# ESQUEMATICO.net
KiCad netlist of a schematic drawn in Altium Designer
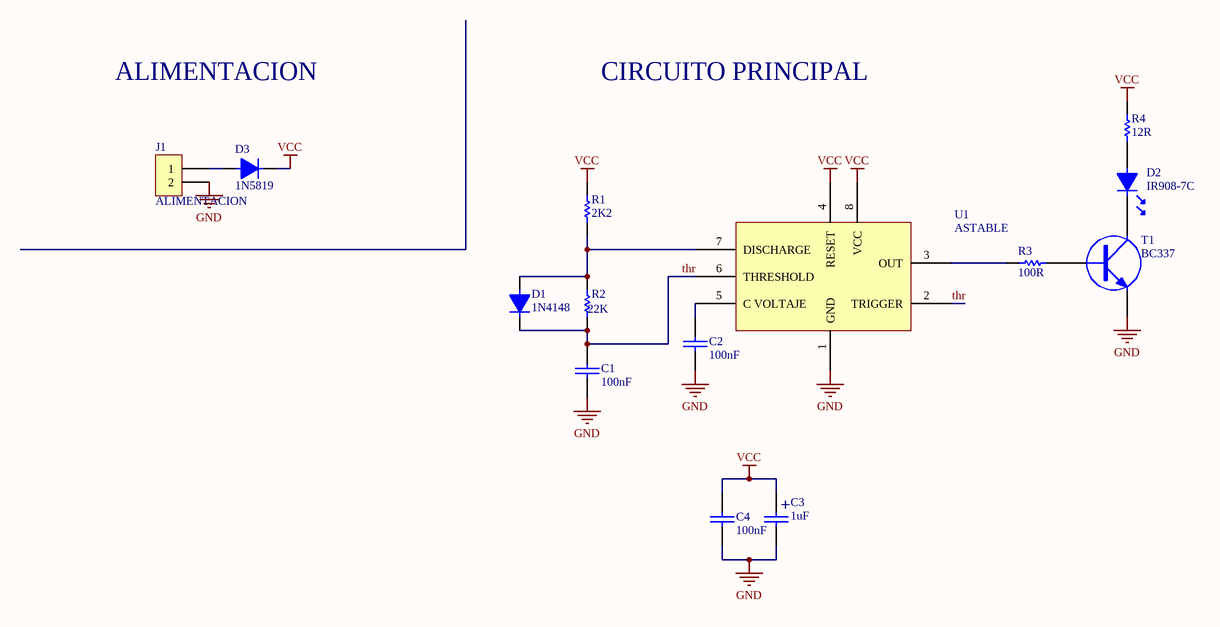
[diagram p0: ESQUEMATICO.SchDoc]

(export (version "E")
  (design (tool "Eeschema 10.0.6"))
  (components
    (comp (ref "C1") (value "100nF") (footprint "CAP100") (libsource (lib "Libreria4") (part "CAP")))
    (comp (ref "C2") (value "100nF") (footprint "CAP200") (libsource (lib "Libreria4") (part "CAP")))
    (comp (ref "C3") (value "1uF") (footprint "CAP100RP") (libsource (lib "Libreria4") (part "CAPPOL")))
    (comp (ref "C4") (value "100nF") (footprint "CAP200") (libsource (lib "Libreria4") (part "CAP")))
    (comp (ref "D1") (value "1N4148") (footprint "DO41") (libsource (lib "Libreria4") (part "DIODO")))
    (comp (ref "D2")
      (value "IR908-7C")
      (footprint "fotodiodo")
      (description "Led infrarrojo")
      (libsource (lib "Libreria4") (part "IR908-7C"))
    )
    (comp (ref "D3") (value "1N5819") (footprint "DO41") (libsource (lib "Libreria4") (part "DIODO")))
    (comp (ref "J1")
      (value "ALIMENTACION")
      (footprint "BORNERA2")
      (libsource (lib "Libreria4") (part "BORNERA 2"))
    )
    (comp (ref "R1") (value "2K2") (footprint "RES400") (libsource (lib "Libreria4") (part "RES")))
    (comp (ref "R2") (value "22K") (footprint "RES400") (libsource (lib "Libreria4") (part "RES")))
    (comp (ref "R3") (value "100R") (footprint "RES400") (libsource (lib "Libreria4") (part "RES")))
    (comp (ref "R4") (value "12R") (footprint "RES400") (libsource (lib "Libreria4") (part "RES")))
    (comp (ref "T1") (value "BC337") (footprint "TO92") (libsource (lib "Libreria4") (part "TRANSISTOR NPN")))
    (comp (ref "U1")
      (value "ASTABLE")
      (footprint "DIP8")
      (description "Timer")
      (libsource (lib "Libreria4") (part "LM555"))
    )
  )
  (nets
    (net (code "1") (name "/thr") (class "Default")
      (node (ref "C1") (pin "1") (pinfunction "1_1") (pintype "passive"))
      (node (ref "D1") (pin "2") (pinfunction "2_2") (pintype "passive"))
      (node (ref "R2") (pin "1") (pinfunction "1_1") (pintype "passive"))
      (node (ref "U1") (pin "2") (pinfunction "TRIGGER_2") (pintype "passive"))
      (node (ref "U1") (pin "6") (pinfunction "THRESHOLD_6") (pintype "passive"))
    )
    (net (code "2") (name "GND") (class "Default")
      (node (ref "C1") (pin "2") (pinfunction "2_2") (pintype "passive"))
      (node (ref "C2") (pin "2") (pinfunction "2_2") (pintype "passive"))
      (node (ref "C3") (pin "2") (pinfunction "2_2") (pintype "passive"))
      (node (ref "C4") (pin "2") (pinfunction "2_2") (pintype "passive"))
      (node (ref "J1") (pin "2") (pinfunction "2_2") (pintype "passive"))
      (node (ref "T1") (pin "3") (pinfunction "E_3") (pintype "passive"))
      (node (ref "U1") (pin "1") (pinfunction "GND_1") (pintype "passive"))
    )
    (net (code "3") (name "Net-(D2-Pad1)") (class "Default")
      (node (ref "D2") (pin "1") (pinfunction "1_1") (pintype "passive"))
      (node (ref "R4") (pin "2") (pinfunction "2_2") (pintype "passive"))
    )
    (net (code "4") (name "Net-(D3-Pad1)") (class "Default")
      (node (ref "D3") (pin "1") (pinfunction "1_1") (pintype "passive"))
      (node (ref "J1") (pin "1") (pinfunction "1_1") (pintype "passive"))
    )
    (net (code "5") (name "Net-(T1-B)") (class "Default")
      (node (ref "R3") (pin "2") (pinfunction "2_2") (pintype "passive"))
      (node (ref "T1") (pin "1") (pinfunction "B_1") (pintype "passive"))
    )
    (net (code "6") (name "Net-(T1-C)") (class "Default")
      (node (ref "D2") (pin "2") (pinfunction "2_2") (pintype "passive"))
      (node (ref "T1") (pin "2") (pinfunction "C_2") (pintype "passive"))
    )
    (net (code "7") (name "Net-(U1-C_VOLTAJE)") (class "Default")
      (node (ref "C2") (pin "1") (pinfunction "1_1") (pintype "passive"))
      (node (ref "U1") (pin "5") (pinfunction "C_VOLTAJE_5") (pintype "passive"))
    )
    (net (code "8") (name "Net-(U1-DISCHARGE)") (class "Default")
      (node (ref "D1") (pin "1") (pinfunction "1_1") (pintype "passive"))
      (node (ref "R1") (pin "2") (pinfunction "2_2") (pintype "passive"))
      (node (ref "R2") (pin "2") (pinfunction "2_2") (pintype "passive"))
      (node (ref "U1") (pin "7") (pinfunction "DISCHARGE_7") (pintype "passive"))
    )
    (net (code "9") (name "Net-(U1-OUT)") (class "Default")
      (node (ref "R3") (pin "1") (pinfunction "1_1") (pintype "passive"))
      (node (ref "U1") (pin "3") (pinfunction "OUT_3") (pintype "passive"))
    )
    (net (code "10") (name "VCC") (class "Default")
      (node (ref "C3") (pin "1") (pinfunction "1_1") (pintype "passive"))
      (node (ref "C4") (pin "1") (pinfunction "1_1") (pintype "passive"))
      (node (ref "D3") (pin "2") (pinfunction "2_2") (pintype "passive"))
      (node (ref "R1") (pin "1") (pinfunction "1_1") (pintype "passive"))
      (node (ref "R4") (pin "1") (pinfunction "1_1") (pintype "passive"))
      (node (ref "U1") (pin "4") (pinfunction "RESET_4") (pintype "passive"))
      (node (ref "U1") (pin "8") (pinfunction "VCC_8") (pintype "passive"))
    )
  )
)
